# R4Nano.net
KiCad netlist of a schematic drawn in EAGLE
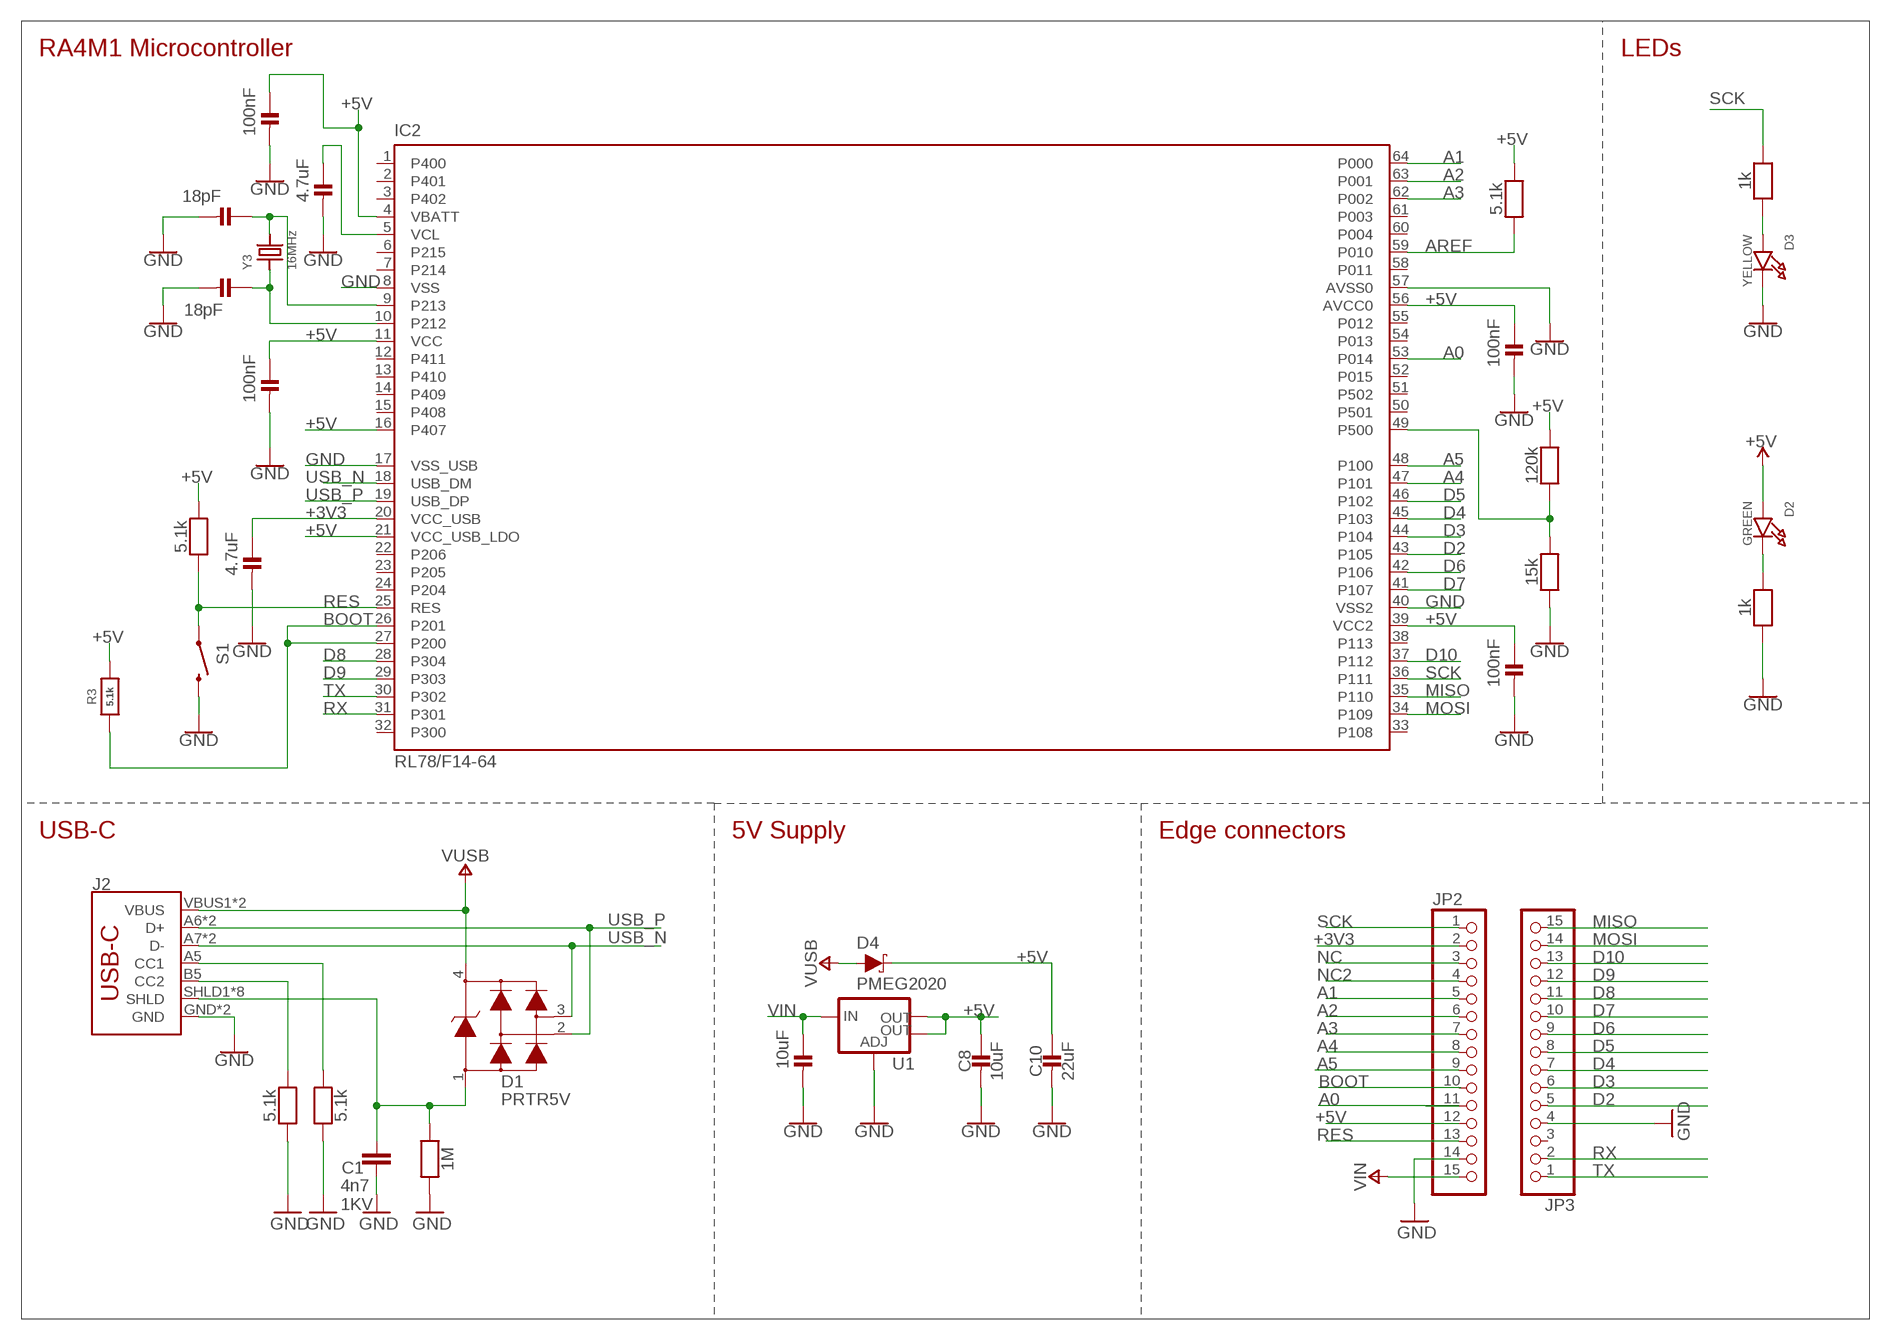
[diagram p0: schematic, sheet 1]

(export (version "E")
  (design (tool "Eeschema 10.0.6"))
  (components
    (comp (ref "C1")
      (value "4n7")
      (footprint "eagle-import:0805-R2013X50N")
      (fields (field (name "MANUFACTURER") "Kemet") (field (name "VOLTAGE") "1KV"))
      (libsource (lib "eagle-import") (part "C-08054.7NF"))
    )
    (comp (ref "C2")
      (value "4.7uF")
      (footprint "eagle-import:_0805MP")
      (libsource (lib "eagle-import") (part "CAP_CERAMIC_0805MP"))
    )
    (comp (ref "C3")
      (value "100nF")
      (footprint "eagle-import:_0805MP")
      (libsource (lib "eagle-import") (part "CAP_CERAMIC_0805MP"))
    )
    (comp (ref "C4")
      (value "100nF")
      (footprint "eagle-import:_0805MP")
      (libsource (lib "eagle-import") (part "CAP_CERAMIC_0805MP"))
    )
    (comp (ref "C5")
      (value "4.7uF")
      (footprint "eagle-import:_0805MP")
      (libsource (lib "eagle-import") (part "CAP_CERAMIC_0805MP"))
    )
    (comp (ref "C6")
      (value "100nF")
      (footprint "eagle-import:_0805MP")
      (libsource (lib "eagle-import") (part "CAP_CERAMIC_0805MP"))
    )
    (comp (ref "C7")
      (value "10uF")
      (footprint "eagle-import:_0805MP")
      (libsource (lib "eagle-import") (part "CAP_CERAMIC_0805MP"))
    )
    (comp (ref "C8")
      (value "10uF")
      (footprint "eagle-import:_0805MP")
      (libsource (lib "eagle-import") (part "CAP_CERAMIC_0805MP"))
    )
    (comp (ref "C9")
      (value "100nF")
      (footprint "eagle-import:_0805MP")
      (libsource (lib "eagle-import") (part "CAP_CERAMIC_0805MP"))
    )
    (comp (ref "C10")
      (value "22uF")
      (footprint "eagle-import:_0805MP")
      (libsource (lib "eagle-import") (part "CAP_CERAMIC_0805MP"))
    )
    (comp (ref "C12")
      (value "18pF")
      (footprint "eagle-import:_0805MP")
      (libsource (lib "eagle-import") (part "CAP_CERAMIC_0805MP"))
    )
    (comp (ref "C13")
      (value "18pF")
      (footprint "eagle-import:_0805MP")
      (libsource (lib "eagle-import") (part "CAP_CERAMIC_0805MP"))
    )
    (comp (ref "D1")
      (value "PRTR5V")
      (footprint "eagle-import:SOT190P230X110-4N")
      (fields (field (name "MANUFACTURER") "NXP"))
      (libsource (lib "eagle-import") (part "PRTR5V0U2X,215"))
    )
    (comp (ref "D2")
      (value "GREEN")
      (footprint "eagle-import:CHIPLED_0805_NOOUTLINE")
      (libsource (lib "eagle-import") (part "LED0805_NOOUTLINE"))
    )
    (comp (ref "D3")
      (value "YELLOW")
      (footprint "eagle-import:CHIPLED_0805_NOOUTLINE")
      (libsource (lib "eagle-import") (part "LED0805_NOOUTLINE"))
    )
    (comp (ref "D4")
      (value "PMEG2020")
      (footprint "eagle-import:SOD-323")
      (libsource (lib "eagle-import") (part "DIODE-SCHOTTKY-BAT60A"))
    )
    (comp (ref "IC2")
      (value "RL78/F14-64")
      (footprint "eagle-import:P-LFQFP64-10X10")
      (libsource (lib "eagle-import") (part "RL78/F14-64"))
    )
    (comp (ref "J2")
      (value "USB_C2-LAYER")
      (footprint "eagle-import:USB-C-16P")
      (libsource (lib "eagle-import") (part "USB_C2-LAYER"))
    )
    (comp (ref "JP2")
      (value "HEADER-1X15")
      (footprint "eagle-import:1X15_ROUND_70")
      (libsource (lib "eagle-import") (part "HEADER-1X15"))
    )
    (comp (ref "JP3")
      (value "HEADER-1X15")
      (footprint "eagle-import:1X15_ROUND_70")
      (libsource (lib "eagle-import") (part "HEADER-1X15"))
    )
    (comp (ref "R1")
      (value "1M")
      (footprint "eagle-import:_0805MP")
      (libsource (lib "eagle-import") (part "RESISTOR_0805MP"))
    )
    (comp (ref "R2")
      (value "5.1k")
      (footprint "eagle-import:_0805MP")
      (libsource (lib "eagle-import") (part "RESISTOR_0805MP"))
    )
    (comp (ref "R3")
      (value "5.1k")
      (footprint "eagle-import:_0805MP")
      (libsource (lib "eagle-import") (part "RESISTOR_0805MP"))
    )
    (comp (ref "R4")
      (value "5.1k")
      (footprint "eagle-import:_0805MP")
      (libsource (lib "eagle-import") (part "RESISTOR_0805MP"))
    )
    (comp (ref "R5")
      (value "1k")
      (footprint "eagle-import:_0805MP")
      (libsource (lib "eagle-import") (part "RESISTOR_0805MP"))
    )
    (comp (ref "R6")
      (value "5.1k")
      (footprint "eagle-import:_0805MP")
      (libsource (lib "eagle-import") (part "RESISTOR_0805MP"))
    )
    (comp (ref "R8")
      (value "5.1k")
      (footprint "eagle-import:_0805MP")
      (libsource (lib "eagle-import") (part "RESISTOR_0805MP"))
    )
    (comp (ref "R10")
      (value "120k")
      (footprint "eagle-import:_0805MP")
      (libsource (lib "eagle-import") (part "RESISTOR_0805MP"))
    )
    (comp (ref "R11")
      (value "15k")
      (footprint "eagle-import:_0805MP")
      (libsource (lib "eagle-import") (part "RESISTOR_0805MP"))
    )
    (comp (ref "R12")
      (value "1k")
      (footprint "eagle-import:_0805MP")
      (libsource (lib "eagle-import") (part "RESISTOR_0805MP"))
    )
    (comp (ref "S1")
      (value "SWITCH-MOMENTARY-2SMD-4.6X2.8MM")
      (footprint "eagle-import:TACTILE_SWITCH_SMD_4.6X2.8MM")
      (libsource (lib "eagle-import") (part "SWITCH-MOMENTARY-2SMD-4.6X2.8MM"))
    )
    (comp (ref "U1")
      (value "V_REG_LM1117SOT223")
      (footprint "eagle-import:SOT223")
      (libsource (lib "eagle-import") (part "V_REG_LM1117SOT223"))
    )
    (comp (ref "Y3")
      (value "16MHz")
      (footprint "eagle-import:CRYSTAL_2.5X2")
      (libsource (lib "eagle-import") (part "CRYSTAL2.5X2.0MM"))
    )
  )
  (nets
    (net (code "1") (name "/+3V3") (class "Default")
      (node (ref "C5") (pin "1") (pinfunction "1_1") (pintype "passive"))
      (node (ref "IC2") (pin "20") (pinfunction "VCC_USB_20") (pintype "power_in"))
      (node (ref "JP2") (pin "2") (pinfunction "2_2") (pintype "passive"))
    )
    (net (code "2") (name "/A0") (class "Default")
      (node (ref "IC2") (pin "53") (pinfunction "P014_53") (pintype "bidirectional"))
      (node (ref "JP2") (pin "11") (pinfunction "11_11") (pintype "passive"))
    )
    (net (code "3") (name "/A1") (class "Default")
      (node (ref "IC2") (pin "64") (pinfunction "P000_64") (pintype "bidirectional"))
      (node (ref "JP2") (pin "5") (pinfunction "5_5") (pintype "passive"))
    )
    (net (code "4") (name "/A2") (class "Default")
      (node (ref "IC2") (pin "63") (pinfunction "P001_63") (pintype "bidirectional"))
      (node (ref "JP2") (pin "6") (pinfunction "6_6") (pintype "passive"))
    )
    (net (code "5") (name "/A3") (class "Default")
      (node (ref "IC2") (pin "62") (pinfunction "P002_62") (pintype "bidirectional"))
      (node (ref "JP2") (pin "7") (pinfunction "7_7") (pintype "passive"))
    )
    (net (code "6") (name "/A4") (class "Default")
      (node (ref "IC2") (pin "47") (pinfunction "P101_47") (pintype "bidirectional"))
      (node (ref "JP2") (pin "8") (pinfunction "8_8") (pintype "passive"))
    )
    (net (code "7") (name "/A5") (class "Default")
      (node (ref "IC2") (pin "48") (pinfunction "P100_48") (pintype "bidirectional"))
      (node (ref "JP2") (pin "9") (pinfunction "9_9") (pintype "passive"))
    )
    (net (code "8") (name "/AREF") (class "Default")
      (node (ref "IC2") (pin "59") (pinfunction "P010_59") (pintype "bidirectional"))
      (node (ref "R2") (pin "2") (pinfunction "2_2") (pintype "passive"))
    )
    (net (code "9") (name "/BOOT") (class "Default")
      (node (ref "IC2") (pin "26") (pinfunction "P201_26") (pintype "bidirectional"))
      (node (ref "IC2") (pin "27") (pinfunction "P200_27") (pintype "bidirectional"))
      (node (ref "JP2") (pin "10") (pinfunction "10_10") (pintype "passive"))
      (node (ref "R3") (pin "2") (pinfunction "2_2") (pintype "passive"))
    )
    (net (code "10") (name "/D2") (class "Default")
      (node (ref "IC2") (pin "43") (pinfunction "P105_43") (pintype "bidirectional"))
      (node (ref "JP3") (pin "5") (pinfunction "5_5") (pintype "passive"))
    )
    (net (code "11") (name "/D3") (class "Default")
      (node (ref "IC2") (pin "44") (pinfunction "P104_44") (pintype "bidirectional"))
      (node (ref "JP3") (pin "6") (pinfunction "6_6") (pintype "passive"))
    )
    (net (code "12") (name "/D4") (class "Default")
      (node (ref "IC2") (pin "45") (pinfunction "P103_45") (pintype "bidirectional"))
      (node (ref "JP3") (pin "7") (pinfunction "7_7") (pintype "passive"))
    )
    (net (code "13") (name "/D5") (class "Default")
      (node (ref "IC2") (pin "46") (pinfunction "P102_46") (pintype "bidirectional"))
      (node (ref "JP3") (pin "8") (pinfunction "8_8") (pintype "passive"))
    )
    (net (code "14") (name "/D6") (class "Default")
      (node (ref "IC2") (pin "42") (pinfunction "P106_42") (pintype "bidirectional"))
      (node (ref "JP3") (pin "9") (pinfunction "9_9") (pintype "passive"))
    )
    (net (code "15") (name "/D7") (class "Default")
      (node (ref "IC2") (pin "41") (pinfunction "P107_41") (pintype "bidirectional"))
      (node (ref "JP3") (pin "10") (pinfunction "10_10") (pintype "passive"))
    )
    (net (code "16") (name "/D8") (class "Default")
      (node (ref "IC2") (pin "28") (pinfunction "P304_28") (pintype "bidirectional"))
      (node (ref "JP3") (pin "11") (pinfunction "11_11") (pintype "passive"))
    )
    (net (code "17") (name "/D9") (class "Default")
      (node (ref "IC2") (pin "29") (pinfunction "P303_29") (pintype "bidirectional"))
      (node (ref "JP3") (pin "12") (pinfunction "12_12") (pintype "passive"))
    )
    (net (code "18") (name "/D10") (class "Default")
      (node (ref "IC2") (pin "37") (pinfunction "P112_37") (pintype "bidirectional"))
      (node (ref "JP3") (pin "13") (pinfunction "13_13") (pintype "passive"))
    )
    (net (code "19") (name "/MISO") (class "Default")
      (node (ref "IC2") (pin "35") (pinfunction "P110_35") (pintype "bidirectional"))
      (node (ref "JP3") (pin "15") (pinfunction "15_15") (pintype "passive"))
    )
    (net (code "20") (name "/MOSI") (class "Default")
      (node (ref "IC2") (pin "34") (pinfunction "P109_34") (pintype "bidirectional"))
      (node (ref "JP3") (pin "14") (pinfunction "14_14") (pintype "passive"))
    )
    (net (code "21") (name "/NC") (class "Default")
      (node (ref "JP2") (pin "3") (pinfunction "3_3") (pintype "passive"))
    )
    (net (code "22") (name "/NC2") (class "Default")
      (node (ref "JP2") (pin "4") (pinfunction "4_4") (pintype "passive"))
    )
    (net (code "23") (name "/RES") (class "Default")
      (node (ref "IC2") (pin "25") (pinfunction "RES_25") (pintype "input"))
      (node (ref "JP2") (pin "13") (pinfunction "13_13") (pintype "passive"))
      (node (ref "R4") (pin "2") (pinfunction "2_2") (pintype "passive"))
      (node (ref "S1") (pin "1") (pinfunction "1_1") (pintype "passive"))
      (node (ref "S1") (pin "2") (pinfunction "1_2") (pintype "passive"))
    )
    (net (code "24") (name "/RX") (class "Default")
      (node (ref "IC2") (pin "31") (pinfunction "P301_31") (pintype "bidirectional"))
      (node (ref "JP3") (pin "2") (pinfunction "2_2") (pintype "passive"))
    )
    (net (code "25") (name "/SCK") (class "Default")
      (node (ref "IC2") (pin "36") (pinfunction "P111_36") (pintype "bidirectional"))
      (node (ref "JP2") (pin "1") (pinfunction "1_1") (pintype "passive"))
      (node (ref "R12") (pin "1") (pinfunction "1_1") (pintype "passive"))
    )
    (net (code "26") (name "/TX") (class "Default")
      (node (ref "IC2") (pin "30") (pinfunction "P302_30") (pintype "bidirectional"))
      (node (ref "JP3") (pin "1") (pinfunction "1_1") (pintype "passive"))
    )
    (net (code "27") (name "/USB_N") (class "Default")
      (node (ref "D1") (pin "3") (pinfunction "3_3") (pintype "passive"))
      (node (ref "IC2") (pin "18") (pinfunction "USB_DM_18") (pintype "bidirectional"))
      (node (ref "J2") (pin "A7") (pinfunction "D-_A7") (pintype "bidirectional"))
      (node (ref "J2") (pin "B7") (pinfunction "D-_B7") (pintype "bidirectional"))
    )
    (net (code "28") (name "/USB_P") (class "Default")
      (node (ref "D1") (pin "2") (pinfunction "2_2") (pintype "passive"))
      (node (ref "IC2") (pin "19") (pinfunction "USB_DP_19") (pintype "bidirectional"))
      (node (ref "J2") (pin "A6") (pinfunction "D+_A6") (pintype "bidirectional"))
      (node (ref "J2") (pin "B6") (pinfunction "D+_B6") (pintype "bidirectional"))
    )
    (net (code "29") (name "GND") (class "Default")
      (node (ref "C1") (pin "2") (pinfunction "2_2") (pintype "passive"))
      (node (ref "C10") (pin "2") (pinfunction "2_2") (pintype "passive"))
      (node (ref "C12") (pin "2") (pinfunction "2_2") (pintype "passive"))
      (node (ref "C13") (pin "2") (pinfunction "2_2") (pintype "passive"))
      (node (ref "C2") (pin "2") (pinfunction "2_2") (pintype "passive"))
      (node (ref "C3") (pin "2") (pinfunction "2_2") (pintype "passive"))
      (node (ref "C4") (pin "2") (pinfunction "2_2") (pintype "passive"))
      (node (ref "C5") (pin "2") (pinfunction "2_2") (pintype "passive"))
      (node (ref "C6") (pin "2") (pinfunction "2_2") (pintype "passive"))
      (node (ref "C7") (pin "2") (pinfunction "2_2") (pintype "passive"))
      (node (ref "C8") (pin "2") (pinfunction "2_2") (pintype "passive"))
      (node (ref "C9") (pin "2") (pinfunction "2_2") (pintype "passive"))
      (node (ref "D3") (pin "C") (pinfunction "C_C") (pintype "passive"))
      (node (ref "IC2") (pin "17") (pinfunction "VSS_USB_17") (pintype "power_in"))
      (node (ref "IC2") (pin "40") (pinfunction "VSS2_40") (pintype "bidirectional"))
      (node (ref "IC2") (pin "57") (pinfunction "AVSS0_57") (pintype "power_in"))
      (node (ref "IC2") (pin "8") (pinfunction "VSS_8") (pintype "power_in"))
      (node (ref "J2") (pin "GND") (pinfunction "GND_GND") (pintype "bidirectional"))
      (node (ref "J2") (pin "GND2") (pinfunction "GND_GND2") (pintype "bidirectional"))
      (node (ref "JP2") (pin "14") (pinfunction "14_14") (pintype "passive"))
      (node (ref "JP3") (pin "4") (pinfunction "4_4") (pintype "passive"))
      (node (ref "R1") (pin "2") (pinfunction "2_2") (pintype "passive"))
      (node (ref "R11") (pin "2") (pinfunction "2_2") (pintype "passive"))
      (node (ref "R5") (pin "1") (pinfunction "1_1") (pintype "passive"))
      (node (ref "R6") (pin "2") (pinfunction "2_2") (pintype "passive"))
      (node (ref "R8") (pin "2") (pinfunction "2_2") (pintype "passive"))
      (node (ref "S1") (pin "3") (pinfunction "2_3") (pintype "passive"))
      (node (ref "S1") (pin "4") (pinfunction "2_4") (pintype "passive"))
      (node (ref "U1") (pin "1") (pinfunction "ADJ_1") (pintype "input"))
    )
    (net (code "30") (name "Net-(C1-Pad1)") (class "Default")
      (node (ref "C1") (pin "1") (pinfunction "1_1") (pintype "passive"))
      (node (ref "D1") (pin "1") (pinfunction "1_1") (pintype "passive"))
      (node (ref "J2") (pin "SHLD1") (pinfunction "SHLD_SHLD1") (pintype "bidirectional"))
      (node (ref "J2") (pin "SHLD2") (pinfunction "SHLD_SHLD2") (pintype "bidirectional"))
      (node (ref "J2") (pin "SHLD3") (pinfunction "SHLD_SHLD3") (pintype "bidirectional"))
      (node (ref "J2") (pin "SHLD4") (pinfunction "SHLD_SHLD4") (pintype "bidirectional"))
      (node (ref "J2") (pin "SHLD5") (pinfunction "SHLD_SHLD5") (pintype "bidirectional"))
      (node (ref "J2") (pin "SHLD6") (pinfunction "SHLD_SHLD6") (pintype "bidirectional"))
      (node (ref "J2") (pin "SHLD7") (pinfunction "SHLD_SHLD7") (pintype "bidirectional"))
      (node (ref "J2") (pin "SHLD8") (pinfunction "SHLD_SHLD8") (pintype "bidirectional"))
      (node (ref "R1") (pin "1") (pinfunction "1_1") (pintype "passive"))
    )
    (net (code "31") (name "Net-(D2-PadC)") (class "Default")
      (node (ref "D2") (pin "C") (pinfunction "C_C") (pintype "passive"))
      (node (ref "R5") (pin "2") (pinfunction "2_2") (pintype "passive"))
    )
    (net (code "32") (name "Net-(D3-PadA)") (class "Default")
      (node (ref "D3") (pin "A") (pinfunction "A_A") (pintype "passive"))
      (node (ref "R12") (pin "2") (pinfunction "2_2") (pintype "passive"))
    )
    (net (code "33") (name "Net-(IC2-P212)") (class "Default")
      (node (ref "C13") (pin "1") (pinfunction "1_1") (pintype "passive"))
      (node (ref "IC2") (pin "10") (pinfunction "P212_10") (pintype "bidirectional"))
      (node (ref "Y3") (pin "1") (pinfunction "1_1") (pintype "passive"))
    )
    (net (code "34") (name "Net-(IC2-P213)") (class "Default")
      (node (ref "C12") (pin "1") (pinfunction "1_1") (pintype "passive"))
      (node (ref "IC2") (pin "9") (pinfunction "P213_9") (pintype "bidirectional"))
      (node (ref "Y3") (pin "3") (pinfunction "2_3") (pintype "passive"))
    )
    (net (code "35") (name "Net-(IC2-P500)") (class "Default")
      (node (ref "IC2") (pin "49") (pinfunction "P500_49") (pintype "bidirectional"))
      (node (ref "R10") (pin "2") (pinfunction "2_2") (pintype "passive"))
      (node (ref "R11") (pin "1") (pinfunction "1_1") (pintype "passive"))
    )
    (net (code "36") (name "Net-(IC2-VCL)") (class "Default")
      (node (ref "C2") (pin "1") (pinfunction "1_1") (pintype "passive"))
      (node (ref "IC2") (pin "5") (pinfunction "VCL_5") (pintype "power_in"))
    )
    (net (code "37") (name "Net-(J2-CC1)") (class "Default")
      (node (ref "J2") (pin "A5") (pinfunction "CC1_A5") (pintype "bidirectional"))
      (node (ref "R8") (pin "1") (pinfunction "1_1") (pintype "passive"))
    )
    (net (code "38") (name "Net-(J2-CC2)") (class "Default")
      (node (ref "J2") (pin "B5") (pinfunction "CC2_B5") (pintype "bidirectional"))
      (node (ref "R6") (pin "1") (pinfunction "1_1") (pintype "passive"))
    )
    (net (code "39") (name "VIN") (class "Default")
      (node (ref "C7") (pin "1") (pinfunction "1_1") (pintype "passive"))
      (node (ref "JP2") (pin "15") (pinfunction "15_15") (pintype "passive"))
      (node (ref "U1") (pin "3") (pinfunction "IN_3") (pintype "input"))
    )
    (net (code "40") (name "VOUT") (class "Default")
      (node (ref "C10") (pin "1") (pinfunction "1_1") (pintype "passive"))
      (node (ref "C3") (pin "1") (pinfunction "1_1") (pintype "passive"))
      (node (ref "C4") (pin "1") (pinfunction "1_1") (pintype "passive"))
      (node (ref "C6") (pin "1") (pinfunction "1_1") (pintype "passive"))
      (node (ref "C8") (pin "1") (pinfunction "1_1") (pintype "passive"))
      (node (ref "C9") (pin "1") (pinfunction "1_1") (pintype "passive"))
      (node (ref "D2") (pin "A") (pinfunction "A_A") (pintype "passive"))
      (node (ref "D4") (pin "C") (pinfunction "C_C") (pintype "passive"))
      (node (ref "IC2") (pin "11") (pinfunction "VCC_11") (pintype "power_in"))
      (node (ref "IC2") (pin "16") (pinfunction "P407_16") (pintype "bidirectional"))
      (node (ref "IC2") (pin "21") (pinfunction "VCC_USB_LDO_21") (pintype "power_in"))
      (node (ref "IC2") (pin "39") (pinfunction "VCC2_39") (pintype "power_in"))
      (node (ref "IC2") (pin "4") (pinfunction "VBATT_4") (pintype "power_in"))
      (node (ref "IC2") (pin "56") (pinfunction "AVCC0_56") (pintype "power_in"))
      (node (ref "JP2") (pin "12") (pinfunction "12_12") (pintype "passive"))
      (node (ref "R10") (pin "1") (pinfunction "1_1") (pintype "passive"))
      (node (ref "R2") (pin "1") (pinfunction "1_1") (pintype "passive"))
      (node (ref "R3") (pin "1") (pinfunction "1_1") (pintype "passive"))
      (node (ref "R4") (pin "1") (pinfunction "1_1") (pintype "passive"))
      (node (ref "U1") (pin "2") (pinfunction "OUT_2") (pintype "output"))
      (node (ref "U1") (pin "4") (pinfunction "OUT_4") (pintype "output"))
    )
    (net (code "41") (name "VUSB") (class "Default")
      (node (ref "D1") (pin "4") (pinfunction "4_4") (pintype "passive"))
      (node (ref "D4") (pin "A") (pinfunction "A_A") (pintype "passive"))
      (node (ref "J2") (pin "VBUS1") (pinfunction "VBUS_VBUS1") (pintype "bidirectional"))
      (node (ref "J2") (pin "VBUS2") (pinfunction "VBUS_VBUS2") (pintype "bidirectional"))
    )
    (net (code "42") (name "unconnected-(IC2-P003-Pad61)") (class "Default")
      (node (ref "IC2") (pin "61") (pinfunction "P003_61") (pintype "bidirectional"))
    )
    (net (code "43") (name "unconnected-(IC2-P004-Pad60)") (class "Default")
      (node (ref "IC2") (pin "60") (pinfunction "P004_60") (pintype "bidirectional"))
    )
    (net (code "44") (name "unconnected-(IC2-P011-Pad58)") (class "Default")
      (node (ref "IC2") (pin "58") (pinfunction "P011_58") (pintype "bidirectional"))
    )
    (net (code "45") (name "unconnected-(IC2-P012-Pad55)") (class "Default")
      (node (ref "IC2") (pin "55") (pinfunction "P012_55") (pintype "bidirectional"))
    )
    (net (code "46") (name "unconnected-(IC2-P013-Pad54)") (class "Default")
      (node (ref "IC2") (pin "54") (pinfunction "P013_54") (pintype "bidirectional"))
    )
    (net (code "47") (name "unconnected-(IC2-P015-Pad52)") (class "Default")
      (node (ref "IC2") (pin "52") (pinfunction "P015_52") (pintype "bidirectional"))
    )
    (net (code "48") (name "unconnected-(IC2-P108-Pad33)") (class "Default")
      (node (ref "IC2") (pin "33") (pinfunction "P108_33") (pintype "bidirectional"))
    )
    (net (code "49") (name "unconnected-(IC2-P113-Pad38)") (class "Default")
      (node (ref "IC2") (pin "38") (pinfunction "P113_38") (pintype "bidirectional"))
    )
    (net (code "50") (name "unconnected-(IC2-P204-Pad24)") (class "Default")
      (node (ref "IC2") (pin "24") (pinfunction "P204_24") (pintype "bidirectional"))
    )
    (net (code "51") (name "unconnected-(IC2-P205-Pad23)") (class "Default")
      (node (ref "IC2") (pin "23") (pinfunction "P205_23") (pintype "bidirectional"))
    )
    (net (code "52") (name "unconnected-(IC2-P206-Pad22)") (class "Default")
      (node (ref "IC2") (pin "22") (pinfunction "P206_22") (pintype "bidirectional"))
    )
    (net (code "53") (name "unconnected-(IC2-P214-Pad7)") (class "Default")
      (node (ref "IC2") (pin "7") (pinfunction "P214_7") (pintype "bidirectional"))
    )
    (net (code "54") (name "unconnected-(IC2-P215-Pad6)") (class "Default")
      (node (ref "IC2") (pin "6") (pinfunction "P215_6") (pintype "bidirectional"))
    )
    (net (code "55") (name "unconnected-(IC2-P300-Pad32)") (class "Default")
      (node (ref "IC2") (pin "32") (pinfunction "P300_32") (pintype "bidirectional"))
    )
    (net (code "56") (name "unconnected-(IC2-P400-Pad1)") (class "Default")
      (node (ref "IC2") (pin "1") (pinfunction "P400_1") (pintype "bidirectional"))
    )
    (net (code "57") (name "unconnected-(IC2-P401-Pad2)") (class "Default")
      (node (ref "IC2") (pin "2") (pinfunction "P401_2") (pintype "bidirectional"))
    )
    (net (code "58") (name "unconnected-(IC2-P402-Pad3)") (class "Default")
      (node (ref "IC2") (pin "3") (pinfunction "P402_3") (pintype "bidirectional"))
    )
    (net (code "59") (name "unconnected-(IC2-P408-Pad15)") (class "Default")
      (node (ref "IC2") (pin "15") (pinfunction "P408_15") (pintype "bidirectional"))
    )
    (net (code "60") (name "unconnected-(IC2-P409-Pad14)") (class "Default")
      (node (ref "IC2") (pin "14") (pinfunction "P409_14") (pintype "bidirectional"))
    )
    (net (code "61") (name "unconnected-(IC2-P410-Pad13)") (class "Default")
      (node (ref "IC2") (pin "13") (pinfunction "P410_13") (pintype "bidirectional"))
    )
    (net (code "62") (name "unconnected-(IC2-P411-Pad12)") (class "Default")
      (node (ref "IC2") (pin "12") (pinfunction "P411_12") (pintype "bidirectional"))
    )
    (net (code "63") (name "unconnected-(IC2-P501-Pad50)") (class "Default")
      (node (ref "IC2") (pin "50") (pinfunction "P501_50") (pintype "bidirectional"))
    )
    (net (code "64") (name "unconnected-(IC2-P502-Pad51)") (class "Default")
      (node (ref "IC2") (pin "51") (pinfunction "P502_51") (pintype "bidirectional"))
    )
    (net (code "65") (name "unconnected-(JP3-Pad3)") (class "Default")
      (node (ref "JP3") (pin "3") (pinfunction "3_3") (pintype "passive"))
    )
  )
)
